# microphone.net
KiCad netlist of a schematic drawn in EAGLE
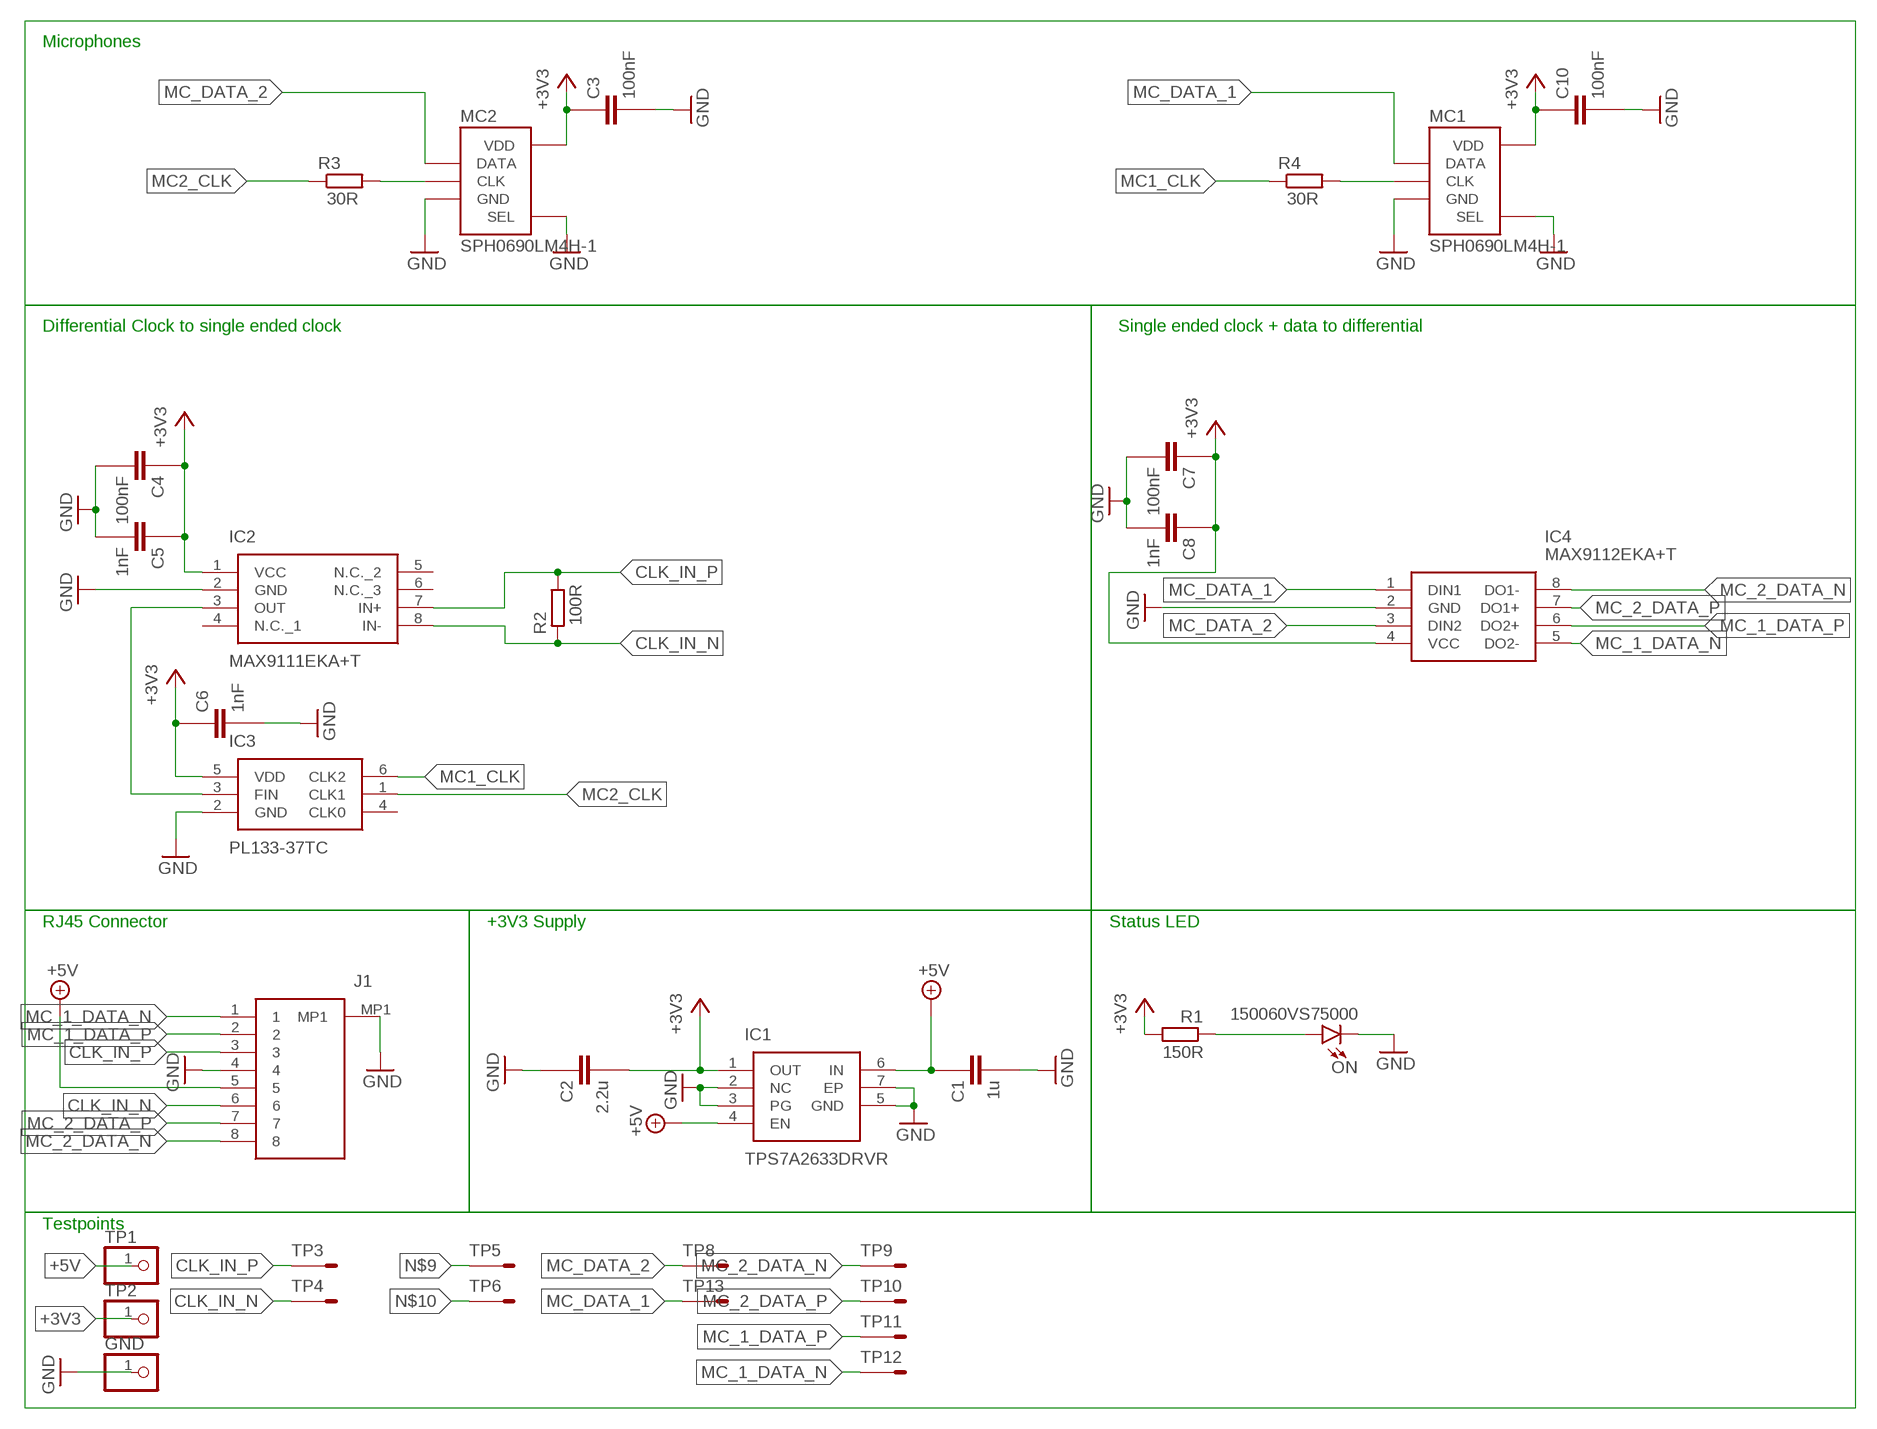
[diagram p0: schematic, sheet 1]

(export (version "E")
  (design (tool "Eeschema 10.0.6"))
  (components
    (comp (ref "C1")
      (value "1u")
      (footprint "eagle-import:CAPC1608X90N")
      (fields
        (field (name "MANUFACTURER_PART_NUMBER") "LMK107B7105KA-T")
        (field (name "MOUSER_PART_NUMBER") "963-LMK107B7105KA-T")
        (field (name "RS_PART_NUMBER") "1721466P")
      )
      (libsource (lib "eagle-import") (part "LMK107B7105KA-T"))
    )
    (comp (ref "C2")
      (value "2.2u")
      (footprint "eagle-import:CAPC1608X90N")
      (fields
        (field (name "MANUFACTURER_PART_NUMBER") "GRM188R71A225KE15D")
        (field (name "MOUSER_PART_NUMBER") "81-GRM188R71A225KE15")
        (field (name "RS_PART_NUMBER") "7235597P")
      )
      (libsource (lib "eagle-import") (part "GRM188R71A225KE15D"))
    )
    (comp (ref "C3")
      (value "100nF")
      (footprint "eagle-import:CAPC1005X55N")
      (fields
        (field (name "MANUFACTURER_PART_NUMBER") "885012205037")
        (field (name "MOUSER_PART_NUMBER") "710-885012205037")
        (field (name "RS_PART_NUMBER") "8391528P")
      )
      (libsource (lib "eagle-import") (part "885012205037"))
    )
    (comp (ref "C4")
      (value "100nF")
      (footprint "eagle-import:CAPC1005X55N")
      (fields
        (field (name "MANUFACTURER_PART_NUMBER") "885012205037")
        (field (name "MOUSER_PART_NUMBER") "710-885012205037")
        (field (name "RS_PART_NUMBER") "8391528P")
      )
      (libsource (lib "eagle-import") (part "885012205037"))
    )
    (comp (ref "C5")
      (value "1nF")
      (footprint "eagle-import:CAPC1005X56N")
      (fields
        (field (name "MANUFACTURER_PART_NUMBER") "0402YC102JAT2A")
        (field (name "MOUSER_PART_NUMBER") "581-0402YC102JAT2A")
        (field (name "RS_PART_NUMBER") "1364217")
      )
      (libsource (lib "eagle-import") (part "0402YC102JAT2A"))
    )
    (comp (ref "C6")
      (value "1nF")
      (footprint "eagle-import:CAPC1005X56N")
      (fields
        (field (name "MANUFACTURER_PART_NUMBER") "0402YC102JAT2A")
        (field (name "MOUSER_PART_NUMBER") "581-0402YC102JAT2A")
        (field (name "RS_PART_NUMBER") "1364217")
      )
      (libsource (lib "eagle-import") (part "0402YC102JAT2A"))
    )
    (comp (ref "C7")
      (value "100nF")
      (footprint "eagle-import:CAPC1005X55N")
      (fields
        (field (name "MANUFACTURER_PART_NUMBER") "885012205037")
        (field (name "MOUSER_PART_NUMBER") "710-885012205037")
        (field (name "RS_PART_NUMBER") "8391528P")
      )
      (libsource (lib "eagle-import") (part "885012205037"))
    )
    (comp (ref "C8")
      (value "1nF")
      (footprint "eagle-import:CAPC1005X56N")
      (fields
        (field (name "MANUFACTURER_PART_NUMBER") "0402YC102JAT2A")
        (field (name "MOUSER_PART_NUMBER") "581-0402YC102JAT2A")
        (field (name "RS_PART_NUMBER") "1364217")
      )
      (libsource (lib "eagle-import") (part "0402YC102JAT2A"))
    )
    (comp (ref "C10")
      (value "100nF")
      (footprint "eagle-import:CAPC1005X55N")
      (fields
        (field (name "MANUFACTURER_PART_NUMBER") "885012205037")
        (field (name "MOUSER_PART_NUMBER") "710-885012205037")
        (field (name "RS_PART_NUMBER") "8391528P")
      )
      (libsource (lib "eagle-import") (part "885012205037"))
    )
    (comp (ref "GND")
      (value "PINHD-1X1")
      (footprint "eagle-import:1X01")
      (libsource (lib "eagle-import") (part "PINHD-1X1"))
    )
    (comp (ref "IC1")
      (value "TPS7A2633DRVR")
      (footprint "eagle-import:TPS7A2633DRVR")
      (fields (field (name "MOUSER_PART_NUMBER") "595-TPS7A2633DRVR"))
      (libsource (lib "eagle-import") (part "TPS7A2633DRVR"))
    )
    (comp (ref "IC2")
      (value "MAX9111EKA+T")
      (footprint "eagle-import:SOT65P280X145-8N")
      (fields (field (name "MOUSER_PART_NUMBER") "700-MAX9111EKAT") (field (name "RS_PART_NUMBER") "1907337"))
      (libsource (lib "eagle-import") (part "MAX9111EKA+T"))
    )
    (comp (ref "IC3")
      (value "PL133-37TC")
      (footprint "eagle-import:SOT95P280X135-6N")
      (fields (field (name "MOUSER_PART_NUMBER") "998-PL133-37TC") (field (name "RS_PART_NUMBER") "1779647"))
      (libsource (lib "eagle-import") (part "PL133-37TC"))
    )
    (comp (ref "IC4")
      (value "MAX9112EKA+T")
      (footprint "eagle-import:SOT65P280X145-8N")
      (fields (field (name "MOUSER_PART_NUMBER") "700-MAX9112EKAT"))
      (libsource (lib "eagle-import") (part "MAX9112EKA+T"))
    )
    (comp (ref "J1")
      (value "RJE231883116T")
      (footprint "eagle-import:RJE231883116T")
      (fields (field (name "MOUSER_PART_NUMBER") "523-RJE231883116T"))
      (libsource (lib "eagle-import") (part "RJE231883116T"))
    )
    (comp (ref "MC1")
      (value "SPH0690LM4H-1")
      (footprint "eagle-import:SPH0690LM4H-1")
      (libsource (lib "eagle-import") (part "SPH0690LM4H-1"))
    )
    (comp (ref "MC2")
      (value "SPH0690LM4H-1")
      (footprint "eagle-import:SPH0690LM4H-1")
      (libsource (lib "eagle-import") (part "SPH0690LM4H-1"))
    )
    (comp (ref "ON")
      (value "150060VS75000")
      (footprint "eagle-import:LEDC1608X80N")
      (fields
        (field (name "MOUSER_PART_NUMBER") "710-150060VS75000")
        (field (name "RS_PART_NUMBER") "8154215P")
      )
      (libsource (lib "eagle-import") (part "150060VS75000"))
    )
    (comp (ref "R1")
      (value "150")
      (footprint "eagle-import:RESC1005X40N")
      (fields
        (field (name "MANUFACTURER_PART_NUMBER") "ERJ-2RKF1500X")
        (field (name "MOUSER_PART_NUMBER") "667-ERJ-2RKF1500X")
      )
      (libsource (lib "eagle-import") (part "ERJ-2RKF1500X"))
    )
    (comp (ref "R2")
      (value "RT0402FRE07100RL")
      (footprint "eagle-import:RESC1005X8N")
      (libsource (lib "eagle-import") (part "RT0402FRE07100RL"))
    )
    (comp (ref "R3")
      (value "100nF")
      (footprint "eagle-import:RESC1005X40N")
      (fields
        (field (name "MANUFACTURER_PART_NUMBER") " RC0402FR-1330RL ")
        (field (name "MOUSER_PART_NUMBER") " 603-RC0402FR-1330RL")
      )
      (libsource (lib "eagle-import") (part "RC0402FR-1330RL"))
    )
    (comp (ref "R4")
      (value "100nF")
      (footprint "eagle-import:RESC1005X40N")
      (fields
        (field (name "MANUFACTURER_PART_NUMBER") " RC0402FR-1330RL ")
        (field (name "MOUSER_PART_NUMBER") " 603-RC0402FR-1330RL")
      )
      (libsource (lib "eagle-import") (part "RC0402FR-1330RL"))
    )
    (comp (ref "TP1")
      (value "PINHD-1X1")
      (footprint "eagle-import:1X01")
      (libsource (lib "eagle-import") (part "PINHD-1X1"))
    )
    (comp (ref "TP2")
      (value "PINHD-1X1")
      (footprint "eagle-import:1X01")
      (libsource (lib "eagle-import") (part "PINHD-1X1"))
    )
    (comp (ref "TP3")
      (value "TESTPOINT_05_05")
      (footprint "eagle-import:TP_05_05")
      (libsource (lib "eagle-import") (part "TESTPOINT_05_05"))
    )
    (comp (ref "TP4")
      (value "TESTPOINT_05_05")
      (footprint "eagle-import:TP_05_05")
      (libsource (lib "eagle-import") (part "TESTPOINT_05_05"))
    )
    (comp (ref "TP5")
      (value "TESTPOINT_05_05")
      (footprint "eagle-import:TP_05_05")
      (libsource (lib "eagle-import") (part "TESTPOINT_05_05"))
    )
    (comp (ref "TP6")
      (value "TESTPOINT_05_05")
      (footprint "eagle-import:TP_05_05")
      (libsource (lib "eagle-import") (part "TESTPOINT_05_05"))
    )
    (comp (ref "TP8")
      (value "TESTPOINT_05_05")
      (footprint "eagle-import:TP_05_05")
      (libsource (lib "eagle-import") (part "TESTPOINT_05_05"))
    )
    (comp (ref "TP9")
      (value "TESTPOINT_05_05")
      (footprint "eagle-import:TP_05_05")
      (libsource (lib "eagle-import") (part "TESTPOINT_05_05"))
    )
    (comp (ref "TP10")
      (value "TESTPOINT_05_05")
      (footprint "eagle-import:TP_05_05")
      (libsource (lib "eagle-import") (part "TESTPOINT_05_05"))
    )
    (comp (ref "TP11")
      (value "TESTPOINT_05_05")
      (footprint "eagle-import:TP_05_05")
      (libsource (lib "eagle-import") (part "TESTPOINT_05_05"))
    )
    (comp (ref "TP12")
      (value "TESTPOINT_05_05")
      (footprint "eagle-import:TP_05_05")
      (libsource (lib "eagle-import") (part "TESTPOINT_05_05"))
    )
    (comp (ref "TP13")
      (value "TESTPOINT_05_05")
      (footprint "eagle-import:TP_05_05")
      (libsource (lib "eagle-import") (part "TESTPOINT_05_05"))
    )
  )
  (nets
    (net (code "1") (name "+3V3") (class "Default")
      (node (ref "C10") (pin "1") (pinfunction "1_1") (pintype "bidirectional"))
      (node (ref "C2") (pin "2") (pinfunction "2_2") (pintype "bidirectional"))
      (node (ref "C3") (pin "1") (pinfunction "1_1") (pintype "bidirectional"))
      (node (ref "C4") (pin "1") (pinfunction "1_1") (pintype "bidirectional"))
      (node (ref "C5") (pin "1") (pinfunction "1_1") (pintype "bidirectional"))
      (node (ref "C6") (pin "1") (pinfunction "1_1") (pintype "bidirectional"))
      (node (ref "C7") (pin "1") (pinfunction "1_1") (pintype "bidirectional"))
      (node (ref "C8") (pin "1") (pinfunction "1_1") (pintype "bidirectional"))
      (node (ref "IC1") (pin "1") (pinfunction "OUT_1") (pintype "bidirectional"))
      (node (ref "IC2") (pin "1") (pinfunction "VCC_1") (pintype "bidirectional"))
      (node (ref "IC3") (pin "5") (pinfunction "VDD_5") (pintype "power_in"))
      (node (ref "IC4") (pin "4") (pinfunction "VCC_4") (pintype "power_in"))
      (node (ref "MC1") (pin "VDD") (pinfunction "VDD_VDD") (pintype "bidirectional"))
      (node (ref "MC2") (pin "VDD") (pinfunction "VDD_VDD") (pintype "bidirectional"))
      (node (ref "R1") (pin "1") (pinfunction "1_1") (pintype "bidirectional"))
      (node (ref "TP2") (pin "1") (pinfunction "1_1") (pintype "passive"))
    )
    (net (code "2") (name "+5V") (class "Default")
      (node (ref "C1") (pin "1") (pinfunction "1_1") (pintype "bidirectional"))
      (node (ref "IC1") (pin "4") (pinfunction "EN_4") (pintype "bidirectional"))
      (node (ref "IC1") (pin "6") (pinfunction "IN_6") (pintype "bidirectional"))
      (node (ref "J1") (pin "5") (pinfunction "5_5") (pintype "bidirectional"))
      (node (ref "TP1") (pin "1") (pinfunction "1_1") (pintype "passive"))
    )
    (net (code "3") (name "CLK_IN_N") (class "Default")
      (node (ref "IC2") (pin "8") (pinfunction "IN-_8") (pintype "bidirectional"))
      (node (ref "J1") (pin "6") (pinfunction "6_6") (pintype "bidirectional"))
      (node (ref "R2") (pin "1") (pinfunction "1_1") (pintype "bidirectional"))
      (node (ref "TP4") (pin "TP") (pinfunction "2_TP") (pintype "passive"))
    )
    (net (code "4") (name "CLK_IN_P") (class "Default")
      (node (ref "IC2") (pin "7") (pinfunction "IN+_7") (pintype "bidirectional"))
      (node (ref "J1") (pin "3") (pinfunction "3_3") (pintype "bidirectional"))
      (node (ref "R2") (pin "2") (pinfunction "2_2") (pintype "bidirectional"))
      (node (ref "TP3") (pin "TP") (pinfunction "2_TP") (pintype "passive"))
    )
    (net (code "5") (name "GND") (class "Default")
      (node (ref "C1") (pin "2") (pinfunction "2_2") (pintype "bidirectional"))
      (node (ref "C10") (pin "2") (pinfunction "2_2") (pintype "bidirectional"))
      (node (ref "C2") (pin "1") (pinfunction "1_1") (pintype "bidirectional"))
      (node (ref "C3") (pin "2") (pinfunction "2_2") (pintype "bidirectional"))
      (node (ref "C4") (pin "2") (pinfunction "2_2") (pintype "bidirectional"))
      (node (ref "C5") (pin "2") (pinfunction "2_2") (pintype "bidirectional"))
      (node (ref "C6") (pin "2") (pinfunction "2_2") (pintype "bidirectional"))
      (node (ref "C7") (pin "2") (pinfunction "2_2") (pintype "bidirectional"))
      (node (ref "C8") (pin "2") (pinfunction "2_2") (pintype "bidirectional"))
      (node (ref "GND") (pin "1") (pinfunction "1_1") (pintype "passive"))
      (node (ref "IC1") (pin "2") (pinfunction "NC_2") (pintype "input"))
      (node (ref "IC1") (pin "3") (pinfunction "PG_3") (pintype "bidirectional"))
      (node (ref "IC1") (pin "5") (pinfunction "GND_5") (pintype "bidirectional"))
      (node (ref "IC1") (pin "7") (pinfunction "EP_7") (pintype "bidirectional"))
      (node (ref "IC2") (pin "2") (pinfunction "GND_2") (pintype "bidirectional"))
      (node (ref "IC3") (pin "2") (pinfunction "GND_2") (pintype "power_in"))
      (node (ref "IC4") (pin "2") (pinfunction "GND_2") (pintype "input"))
      (node (ref "J1") (pin "4") (pinfunction "4_4") (pintype "bidirectional"))
      (node (ref "J1") (pin "MP1") (pinfunction "MP1_MP1") (pintype "bidirectional"))
      (node (ref "MC1") (pin "GND") (pinfunction "GND_GND") (pintype "bidirectional"))
      (node (ref "MC1") (pin "SEL") (pinfunction "SEL_SEL") (pintype "bidirectional"))
      (node (ref "MC2") (pin "GND") (pinfunction "GND_GND") (pintype "bidirectional"))
      (node (ref "MC2") (pin "SEL") (pinfunction "SEL_SEL") (pintype "bidirectional"))
      (node (ref "ON") (pin "1") (pinfunction "K_1") (pintype "bidirectional"))
    )
    (net (code "6") (name "MC1_CLK") (class "Default")
      (node (ref "IC3") (pin "6") (pinfunction "CLK2_6") (pintype "output"))
      (node (ref "R4") (pin "1") (pinfunction "1_1") (pintype "bidirectional"))
    )
    (net (code "7") (name "MC2_CLK") (class "Default")
      (node (ref "IC3") (pin "1") (pinfunction "CLK1_1") (pintype "output"))
      (node (ref "R3") (pin "1") (pinfunction "1_1") (pintype "bidirectional"))
    )
    (net (code "8") (name "MC_1_DATA_N") (class "Default")
      (node (ref "IC4") (pin "5") (pinfunction "DO2-_5") (pintype "bidirectional"))
      (node (ref "J1") (pin "1") (pinfunction "1_1") (pintype "bidirectional"))
      (node (ref "TP12") (pin "TP") (pinfunction "2_TP") (pintype "passive"))
    )
    (net (code "9") (name "MC_1_DATA_P") (class "Default")
      (node (ref "IC4") (pin "6") (pinfunction "DO2+_6") (pintype "bidirectional"))
      (node (ref "J1") (pin "2") (pinfunction "2_2") (pintype "bidirectional"))
      (node (ref "TP11") (pin "TP") (pinfunction "2_TP") (pintype "passive"))
    )
    (net (code "10") (name "MC_2_DATA_N") (class "Default")
      (node (ref "IC4") (pin "8") (pinfunction "DO1-_8") (pintype "bidirectional"))
      (node (ref "J1") (pin "8") (pinfunction "8_8") (pintype "bidirectional"))
      (node (ref "TP9") (pin "TP") (pinfunction "2_TP") (pintype "passive"))
    )
    (net (code "11") (name "MC_2_DATA_P") (class "Default")
      (node (ref "IC4") (pin "7") (pinfunction "DO1+_7") (pintype "bidirectional"))
      (node (ref "J1") (pin "7") (pinfunction "7_7") (pintype "bidirectional"))
      (node (ref "TP10") (pin "TP") (pinfunction "2_TP") (pintype "passive"))
    )
    (net (code "12") (name "MC_DATA_1") (class "Default")
      (node (ref "IC4") (pin "1") (pinfunction "DIN1_1") (pintype "power_in"))
      (node (ref "MC1") (pin "DATA") (pinfunction "DATA_DATA") (pintype "bidirectional"))
      (node (ref "TP13") (pin "TP") (pinfunction "2_TP") (pintype "passive"))
    )
    (net (code "13") (name "MC_DATA_2") (class "Default")
      (node (ref "IC4") (pin "3") (pinfunction "DIN2_3") (pintype "input"))
      (node (ref "MC2") (pin "DATA") (pinfunction "DATA_DATA") (pintype "bidirectional"))
      (node (ref "TP8") (pin "TP") (pinfunction "2_TP") (pintype "passive"))
    )
    (net (code "14") (name "N$9") (class "Default")
      (node (ref "MC2") (pin "CLK") (pinfunction "CLK_CLK") (pintype "bidirectional"))
      (node (ref "R3") (pin "2") (pinfunction "2_2") (pintype "bidirectional"))
      (node (ref "TP5") (pin "TP") (pinfunction "2_TP") (pintype "passive"))
    )
    (net (code "15") (name "N$10") (class "Default")
      (node (ref "MC1") (pin "CLK") (pinfunction "CLK_CLK") (pintype "bidirectional"))
      (node (ref "R4") (pin "2") (pinfunction "2_2") (pintype "bidirectional"))
      (node (ref "TP6") (pin "TP") (pinfunction "2_TP") (pintype "passive"))
    )
    (net (code "16") (name "Net-(IC2-OUT)") (class "Default")
      (node (ref "IC2") (pin "3") (pinfunction "OUT_3") (pintype "bidirectional"))
      (node (ref "IC3") (pin "3") (pinfunction "FIN_3") (pintype "input"))
    )
    (net (code "17") (name "Net-(ON-A)") (class "Default")
      (node (ref "ON") (pin "2") (pinfunction "A_2") (pintype "bidirectional"))
      (node (ref "R1") (pin "2") (pinfunction "2_2") (pintype "bidirectional"))
    )
    (net (code "18") (name "unconnected-(IC2-N.C._1-Pad4)") (class "Default")
      (node (ref "IC2") (pin "4") (pinfunction "N.C._1_4") (pintype "bidirectional"))
    )
    (net (code "19") (name "unconnected-(IC2-N.C._2-Pad5)") (class "Default")
      (node (ref "IC2") (pin "5") (pinfunction "N.C._2_5") (pintype "bidirectional"))
    )
    (net (code "20") (name "unconnected-(IC2-N.C._3-Pad6)") (class "Default")
      (node (ref "IC2") (pin "6") (pinfunction "N.C._3_6") (pintype "bidirectional"))
    )
    (net (code "21") (name "unconnected-(IC3-CLK0-Pad4)") (class "Default")
      (node (ref "IC3") (pin "4") (pinfunction "CLK0_4") (pintype "output"))
    )
  )
)
